# MEMS_RF.net
KiCad netlist of a schematic drawn in Altium Designer
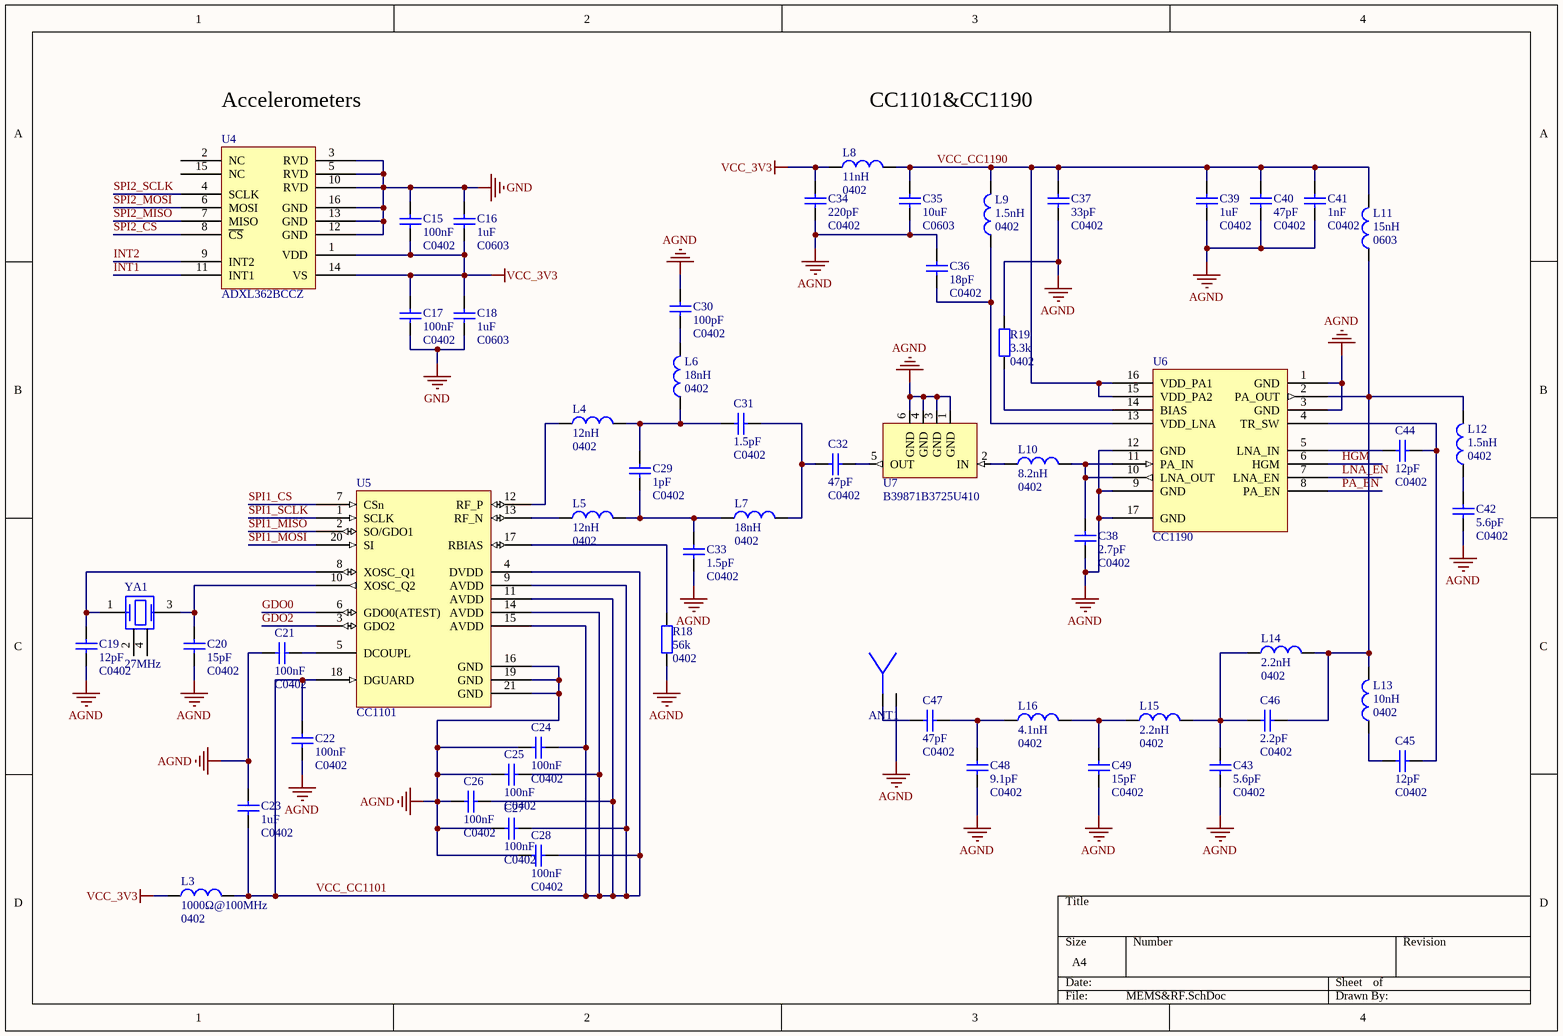
[diagram p0: MEMS&RF.SchDoc]

(export (version "E")
  (design (tool "Eeschema 10.0.6"))
  (components
    (comp (ref "ANT1")
      (value "ANT")
      (footprint "SMB-xg")
      (description "Antenna,GPS_ANT_IPX")
      (libsource (lib "RFID_CC1101_869MHz") (part "ANT"))
    )
    (comp (ref "C15")
      (value "100nF")
      (footprint "0402")
      (description "Capacitor (0402,X7R,100nF,DC 50V,±10%) TDK")
      (fields (field (name "PACKAGEREFERENCE") "C0402") (field (name "PUBLISHER") "Altium Limited"))
      (libsource (lib "GPS_NB") (part "C1005X7R1H104K050BE"))
    )
    (comp (ref "C16")
      (value "1uF")
      (footprint "1608[0603]")
      (description "Capacitor (0603,X5R,1uF,DC 10V,+/-10%) TDK")
      (fields (field (name "PACKAGEREFERENCE") "C0603") (field (name "PUBLISHER") "Altium Limited"))
      (libsource (lib "GPS_NB") (part "CGA3E2X5R1A105K080AA"))
    )
    (comp (ref "C17")
      (value "100nF")
      (footprint "0402")
      (description "Capacitor (0402,X7R,100nF,DC 50V,±10%) TDK")
      (fields (field (name "PACKAGEREFERENCE") "C0402") (field (name "PUBLISHER") "Altium Limited"))
      (libsource (lib "GPS_NB") (part "C1005X7R1H104K050BE"))
    )
    (comp (ref "C18")
      (value "1uF")
      (footprint "1608[0603]")
      (description "Capacitor (0603,X5R,1uF,DC 10V,+/-10%) TDK")
      (fields (field (name "PACKAGEREFERENCE") "C0603") (field (name "PUBLISHER") "Altium Limited"))
      (libsource (lib "GPS_NB") (part "CGA3E2X5R1A105K080AA"))
    )
    (comp (ref "C19")
      (value "12pF")
      (footprint "0402")
      (description "Capacitor (0402,NP0,12pF,DC 50V,±5%) Murata")
      (fields (field (name "PACKAGEREFERENCE") "C0402") (field (name "PUBLISHER") "Altium Limited"))
      (libsource (lib "RFID_CC1101_869MHz") (part "GRM1555C1H120JZ01D"))
    )
    (comp (ref "C20")
      (value "15pF")
      (footprint "0402")
      (description "Capacitor (0402,NP0,15pF,DC 50V,±5%) Murata")
      (fields (field (name "PACKAGEREFERENCE") "C0402") (field (name "PUBLISHER") "Altium Limited"))
      (libsource (lib "RFID_CC1101_869MHz") (part "GRM1555C1H150JZ01D"))
    )
    (comp (ref "C21")
      (value "100nF")
      (footprint "0402")
      (description "Capacitor (0402,X5R,100nF,DC 10V,±10%) Murata")
      (fields (field (name "PACKAGEREFERENCE") "C0402") (field (name "PUBLISHER") "Altium Limited"))
      (libsource (lib "RFID_CC1101_869MHz") (part "GRM155R71A104KA01D"))
    )
    (comp (ref "C22")
      (value "100nF")
      (footprint "0402")
      (description "Capacitor (0402,X5R,100nF,DC 10V,±10%) Murata")
      (fields (field (name "PACKAGEREFERENCE") "C0402") (field (name "PUBLISHER") "Altium Limited"))
      (libsource (lib "RFID_CC1101_869MHz") (part "GRM155R71A104KA01D"))
    )
    (comp (ref "C23")
      (value "1uF")
      (footprint "0402")
      (description "Capacitor (0402,X5R,1uF,DC 6.3V,±10%) Murata")
      (fields (field (name "PACKAGEREFERENCE") "C0402") (field (name "PUBLISHER") "Altium Limited"))
      (libsource (lib "RFID_CC1101_869MHz") (part "GRM155R60J105KE19D"))
    )
    (comp (ref "C24")
      (value "100nF")
      (footprint "0402")
      (description "Capacitor (0402,X5R,100nF,DC 10V,±10%) Murata")
      (fields (field (name "PACKAGEREFERENCE") "C0402") (field (name "PUBLISHER") "Altium Limited"))
      (libsource (lib "RFID_CC1101_869MHz") (part "GRM155R71A104KA01D"))
    )
    (comp (ref "C25")
      (value "100nF")
      (footprint "0402")
      (description "Capacitor (0402,X5R,100nF,DC 10V,±10%) Murata")
      (fields (field (name "PACKAGEREFERENCE") "C0402") (field (name "PUBLISHER") "Altium Limited"))
      (libsource (lib "RFID_CC1101_869MHz") (part "GRM155R71A104KA01D"))
    )
    (comp (ref "C26")
      (value "100nF")
      (footprint "0402")
      (description "Capacitor (0402,X5R,100nF,DC 10V,±10%) Murata")
      (fields (field (name "PACKAGEREFERENCE") "C0402") (field (name "PUBLISHER") "Altium Limited"))
      (libsource (lib "RFID_CC1101_869MHz") (part "GRM155R71A104KA01D"))
    )
    (comp (ref "C27")
      (value "100nF")
      (footprint "0402")
      (description "Capacitor (0402,X5R,100nF,DC 10V,±10%) Murata")
      (fields (field (name "PACKAGEREFERENCE") "C0402") (field (name "PUBLISHER") "Altium Limited"))
      (libsource (lib "RFID_CC1101_869MHz") (part "GRM155R71A104KA01D"))
    )
    (comp (ref "C28")
      (value "100nF")
      (footprint "0402")
      (description "Capacitor (0402,X5R,100nF,DC 10V,±10%) Murata")
      (fields (field (name "PACKAGEREFERENCE") "C0402") (field (name "PUBLISHER") "Altium Limited"))
      (libsource (lib "RFID_CC1101_869MHz") (part "GRM155R71A104KA01D"))
    )
    (comp (ref "C29")
      (value "1pF")
      (footprint "0402")
      (description "Capacitor (0402,NP0,1pF,DC 50V,±0.25pF) Murata")
      (fields (field (name "PACKAGEREFERENCE") "C0402") (field (name "PUBLISHER") "Altium Limited"))
      (libsource (lib "RFID_CC1101_869MHz") (part "GRM1555C1H1R0CZ01D"))
    )
    (comp (ref "C30")
      (value "100pF")
      (footprint "0402")
      (description "Capacitor (0402,NP0,100pF,DC 50V,±5%) Murata")
      (fields (field (name "PACKAGEREFERENCE") "C0402") (field (name "PUBLISHER") "Altium Limited"))
      (libsource (lib "RFID_CC1101_869MHz") (part "GRM1555C1H101JZ01D"))
    )
    (comp (ref "C31")
      (value "1.5pF")
      (footprint "0402")
      (description "Capacitor (0402,NP0,1.5pF,DC 50V,±0.25pF) Murata")
      (fields (field (name "PACKAGEREFERENCE") "C0402") (field (name "PUBLISHER") "Altium Limited"))
      (libsource (lib "RFID_CC1101_869MHz") (part "GRM1555C1H1R5CZ01D"))
    )
    (comp (ref "C32")
      (value "47pF")
      (footprint "0402")
      (description "Capacitor (0402,NP0,47pF,DC 50V,±5%) Murata")
      (fields (field (name "PACKAGEREFERENCE") "C0402") (field (name "PUBLISHER") "Altium Limited"))
      (libsource (lib "RFID_CC1101_869MHz") (part "GRM1555C1H470JZ01D"))
    )
    (comp (ref "C33")
      (value "1.5pF")
      (footprint "0402")
      (description "Capacitor (0402,NP0,1.5pF,DC 50V,±0.25pF) Murata")
      (fields (field (name "PACKAGEREFERENCE") "C0402") (field (name "PUBLISHER") "Altium Limited"))
      (libsource (lib "RFID_CC1101_869MHz") (part "GRM1555C1H1R5CZ01D"))
    )
    (comp (ref "C34")
      (value "220pF")
      (footprint "0402")
      (description "Capacitor (0402,NP0,220pF,DC 50V,±5%) Murata")
      (fields (field (name "PACKAGEREFERENCE") "C0402") (field (name "PUBLISHER") "Altium Limited"))
      (libsource (lib "RFID_CC1101_869MHz") (part "GRM1555C1H221JA01D"))
    )
    (comp (ref "C35")
      (value "10uF")
      (footprint "1608[0603]")
      (description "Capacitor (0603,X5R,10uF,DC 4V,+/-20%) Murata")
      (fields (field (name "PACKAGEREFERENCE") "C0603") (field (name "PUBLISHER") "Altium Limited"))
      (libsource (lib "RFID_CC1101_869MHz") (part "GRM188R60G106ME47D"))
    )
    (comp (ref "C36")
      (value "18pF")
      (footprint "0402")
      (description "Capacitor (0402,NP0,18pF,DC 25V,±5%) Murata")
      (fields (field (name "PACKAGEREFERENCE") "C0402") (field (name "PUBLISHER") "Altium Limited"))
      (libsource (lib "RFID_CC1101_869MHz") (part "GRM1555C1H180JZ01D"))
    )
    (comp (ref "C37")
      (value "33pF")
      (footprint "0402")
      (description "Capacitor (0402,NP0,33pF,DC 50V,±5%) Murata")
      (fields (field (name "PACKAGEREFERENCE") "C0402") (field (name "PUBLISHER") "Altium Limited"))
      (libsource (lib "RFID_CC1101_869MHz") (part "GRM1555C1H330JZ01D"))
    )
    (comp (ref "C38")
      (value "2.7pF")
      (footprint "0402")
      (description "Capacitor (0402,NP0,2.7pF,DC 50V,±0.25pF) Murata")
      (fields (field (name "PACKAGEREFERENCE") "C0402") (field (name "PUBLISHER") "Altium Limited"))
      (libsource (lib "RFID_CC1101_869MHz") (part "GRM1555C1H2R7CZ01D"))
    )
    (comp (ref "C39")
      (value "1uF")
      (footprint "0402")
      (description "Capacitor (0402,X5R,1uF,DC 6.3V,±10%) Murata")
      (fields (field (name "PACKAGEREFERENCE") "C0402") (field (name "PUBLISHER") "Altium Limited"))
      (libsource (lib "RFID_CC1101_869MHz") (part "GRM155R60J105KE19D"))
    )
    (comp (ref "C40")
      (value "47pF")
      (footprint "0402")
      (description "Capacitor (0402,NP0,47pF,DC 50V,±5%) Murata")
      (fields (field (name "PACKAGEREFERENCE") "C0402") (field (name "PUBLISHER") "Altium Limited"))
      (libsource (lib "RFID_CC1101_869MHz") (part "GRM1555C1H470JZ01D"))
    )
    (comp (ref "C41")
      (value "1nF")
      (footprint "0402")
      (description "Capacitor (0402,NP0,1nF,DC 50V,±5%) Murata")
      (fields (field (name "PACKAGEREFERENCE") "C0402") (field (name "PUBLISHER") "Altium Limited"))
      (libsource (lib "RFID_CC1101_869MHz") (part "GRM1555C1H102JA01D"))
    )
    (comp (ref "C42")
      (value "5.6pF")
      (footprint "0402")
      (description "Capacitor (0402,NP0,5.6pF,DC 50V,±0.25pF) Murata")
      (fields (field (name "PACKAGEREFERENCE") "C0402") (field (name "PUBLISHER") "Altium Limited"))
      (libsource (lib "RFID_CC1101_869MHz") (part "GRM1555C1H5R6CZ01D"))
    )
    (comp (ref "C43")
      (value "5.6pF")
      (footprint "0402")
      (description "Capacitor (0402,NP0,5.6pF,DC 50V,±0.25pF) Murata")
      (fields (field (name "PACKAGEREFERENCE") "C0402") (field (name "PUBLISHER") "Altium Limited"))
      (libsource (lib "RFID_CC1101_869MHz") (part "GRM1555C1H5R6CZ01D"))
    )
    (comp (ref "C44")
      (value "12pF")
      (footprint "0402")
      (description "Capacitor (0402,NP0,12pF,DC 50V,±5%) Murata")
      (fields (field (name "PACKAGEREFERENCE") "C0402") (field (name "PUBLISHER") "Altium Limited"))
      (libsource (lib "RFID_CC1101_869MHz") (part "GRM1555C1H120JZ01D"))
    )
    (comp (ref "C45")
      (value "12pF")
      (footprint "0402")
      (description "Capacitor (0402,NP0,12pF,DC 50V,±5%) Murata")
      (fields (field (name "PACKAGEREFERENCE") "C0402") (field (name "PUBLISHER") "Altium Limited"))
      (libsource (lib "RFID_CC1101_869MHz") (part "GRM1555C1H120JZ01D"))
    )
    (comp (ref "C46")
      (value "2.2pF")
      (footprint "0402")
      (description "Capacitor (0402,NP0,2.2pF,DC 50V,±0.25pF) Murata")
      (fields (field (name "PACKAGEREFERENCE") "C0402") (field (name "PUBLISHER") "Altium Limited"))
      (libsource (lib "RFID_CC1101_869MHz") (part "GRM1555C1H2R2CZ01"))
    )
    (comp (ref "C47")
      (value "47pF")
      (footprint "0402")
      (description "Capacitor (0402,NP0,47pF,DC 50V,±5%) Murata")
      (fields (field (name "PACKAGEREFERENCE") "C0402") (field (name "PUBLISHER") "Altium Limited"))
      (libsource (lib "RFID_CC1101_869MHz") (part "GRM1555C1H470JZ01D"))
    )
    (comp (ref "C48")
      (value "9.1pF")
      (footprint "0402")
      (description "Capacitor (0402,NP0,9.1pF,DC 50V,±0.25pF) Murata")
      (fields (field (name "PACKAGEREFERENCE") "C0402") (field (name "PUBLISHER") "Altium Limited"))
      (libsource (lib "RFID_CC1101_869MHz") (part "GRM1555C1H9R1CA01D"))
    )
    (comp (ref "C49")
      (value "15pF")
      (footprint "0402")
      (description "Capacitor (0402,NP0,15pF,DC 50V,±5%) Murata")
      (fields (field (name "PACKAGEREFERENCE") "C0402") (field (name "PUBLISHER") "Altium Limited"))
      (libsource (lib "RFID_CC1101_869MHz") (part "GRM1555C1H150JZ01D"))
    )
    (comp (ref "L3")
      (value "1000Ω@100MHz")
      (footprint "0402")
      (description "Inductor,EMI filter bead, 1000Ω@100MHz 250mA, 0402 1k ohms Tape GHz Band Gen Use, Murata")
      (fields (field (name "PACKAGEREFERENCE") "0402") (field (name "PUBLISHER") "Altium Limited"))
      (libsource (lib "RFID_CC1101_869MHz") (part "BLM15HG102SN1D"))
    )
    (comp (ref "L4")
      (value "12nH")
      (footprint "0402")
      (description "Inductor, 12n, 0402, ±5%, wire-wound type Murata")
      (fields (field (name "PACKAGEREFERENCE") "0402") (field (name "PUBLISHER") "Altium Limited"))
      (libsource (lib "RFID_CC1101_869MHz") (part "LQW15AN12NJ00D"))
    )
    (comp (ref "L5")
      (value "12nH")
      (footprint "0402")
      (description "Inductor, 12n, 0402, ±5%, wire-wound type Murata")
      (fields (field (name "PACKAGEREFERENCE") "0402") (field (name "PUBLISHER") "Altium Limited"))
      (libsource (lib "RFID_CC1101_869MHz") (part "LQW15AN12NJ00D"))
    )
    (comp (ref "L6")
      (value "18nH")
      (footprint "0402")
      (description "Inductor, 18n, 0402, ±5%, wire-wound type Murata")
      (fields (field (name "PACKAGEREFERENCE") "0402") (field (name "PUBLISHER") "Altium Limited"))
      (libsource (lib "RFID_CC1101_869MHz") (part "LQW15AN18NJ00D"))
    )
    (comp (ref "L7")
      (value "18nH")
      (footprint "0402")
      (description "Inductor, 18n, 0402, ±5%, wire-wound type Murata")
      (fields (field (name "PACKAGEREFERENCE") "0402") (field (name "PUBLISHER") "Altium Limited"))
      (libsource (lib "RFID_CC1101_869MHz") (part "LQW15AN18NJ00D"))
    )
    (comp (ref "L8")
      (value "11nH")
      (footprint "0402")
      (description "Inductor, 11n, 0402, ±5%, wire-wound type Murata")
      (fields (field (name "PACKAGEREFERENCE") "0402") (field (name "PUBLISHER") "Altium Limited"))
      (libsource (lib "RFID_CC1101_869MHz") (part "LQW15AN11NJ00"))
    )
    (comp (ref "L9")
      (value "1.5nH")
      (footprint "0402")
      (description "Inductor, 1n5, 0402, Monolithic type, +/-0.3 nH Murata")
      (fields (field (name "PACKAGEREFERENCE") "0402") (field (name "PUBLISHER") "Altium Limited"))
      (libsource (lib "RFID_CC1101_869MHz") (part "LQG15HS1N5S02D"))
    )
    (comp (ref "L10")
      (value "8.2nH")
      (footprint "0402")
      (description "Inductor, 8n2, 0402, ±5%\r\nMurata")
      (fields (field (name "PACKAGEREFERENCE") "0402") (field (name "PUBLISHER") "Altium Limited"))
      (libsource (lib "RFID_CC1101_869MHz") (part "LQG15HS8N2J02D"))
    )
    (comp (ref "L11")
      (value "15nH")
      (footprint "1608[0603]")
      (description "Inductor, 15n, 0603, ±5%, wire-wound type Murata")
      (fields (field (name "PACKAGEREFERENCE") "0603") (field (name "PUBLISHER") "Altium Limited"))
      (libsource (lib "RFID_CC1101_869MHz") (part "LQW18AN15NJ00"))
    )
    (comp (ref "L12")
      (value "1.5nH")
      (footprint "0402")
      (description "Inductor, 1n5, 0402, Monolithic type, +/-0.3 nH Murata")
      (fields (field (name "PACKAGEREFERENCE") "0402") (field (name "PUBLISHER") "Altium Limited"))
      (libsource (lib "RFID_CC1101_869MHz") (part "LQG15HS1N5S02D"))
    )
    (comp (ref "L13")
      (value "10nH")
      (footprint "0402")
      (description "Inductor, 10n, 0402, ±5%, wire-wound type Murata")
      (fields (field (name "PACKAGEREFERENCE") "0402") (field (name "PUBLISHER") "Altium Limited"))
      (libsource (lib "RFID_CC1101_869MHz") (part "LQW15AN10NJ00D"))
    )
    (comp (ref "L14")
      (value "2.2nH")
      (footprint "0402")
      (description "Inductor, 2n2, 0402, wire-wound type, +/- 0.2 nH Murata")
      (fields (field (name "PACKAGEREFERENCE") "0402") (field (name "PUBLISHER") "Altium Limited"))
      (libsource (lib "RFID_CC1101_869MHz") (part "LQW15AN2N2C10D"))
    )
    (comp (ref "L15")
      (value "2.2nH")
      (footprint "0402")
      (description "Inductor, 2n2, 0402, wire-wound type, +/- 0.2 nH Murata")
      (fields (field (name "PACKAGEREFERENCE") "0402") (field (name "PUBLISHER") "Altium Limited"))
      (libsource (lib "RFID_CC1101_869MHz") (part "LQW15AN2N2C10D"))
    )
    (comp (ref "L16")
      (value "4.1nH")
      (footprint "0402")
      (description "Inductor, 4n1, 0402, +/-0.2nH, wire-wound type Murata")
      (fields (field (name "PACKAGEREFERENCE") "0402") (field (name "PUBLISHER") "Altium Limited"))
      (libsource (lib "RFID_CC1101_869MHz") (part "LQW15AN4N1C00"))
    )
    (comp (ref "R18")
      (value "56k")
      (footprint "RESC1005X04N")
      (description "Resistor, 56k ohms, 0402, ±1% Koa")
      (fields (field (name "PACKAGEREFERENCE") "0402"))
      (libsource (lib "RFID_CC1101_869MHz") (part "RK73H1ETTP5602F"))
    )
    (comp (ref "R19")
      (value "3.3k")
      (footprint "RESC1005X04N")
      (description "Resistor, 3.3k ohms, 0402, ±1% Koa")
      (fields (field (name "PACKAGEREFERENCE") "0402"))
      (libsource (lib "RFID_CC1101_869MHz") (part "RK73H1ETTP3301F"))
    )
    (comp (ref "U4")
      (value "ADXL362BCCZ")
      (footprint "LGA_CC-16-4")
      (description "ADXL362, LGA, CC-16-4.")
      (libsource (lib "GPS_NB") (part "ADXL362BCCZ"))
    )
    (comp (ref "U5")
      (value "CC1101")
      (footprint "QFN50P400X400X100_HS-21N")
      (description "Low-Power Sub-1GHz RF Transceiver")
      (libsource (lib "RFID_CC1101_869MHz") (part "CC1101"))
    )
    (comp (ref "U6")
      (value "CC1190")
      (footprint "QFN65P400X400X100_HS-17N")
      (description "850– 950MHzRFFrontEnd")
      (libsource (lib "RFID_CC1101_869MHz") (part "CC1190"))
    )
    (comp (ref "U7")
      (value "B39871B3725U410")
      (footprint "DCC6C")
      (libsource (lib "RFID_CC1101_869MHz") (part "B39871B3725U410"))
    )
    (comp (ref "YA1")
      (value "27MHz")
      (footprint "XTAL-SMT-4P")
      (description "Crystal, 27.000000MHz, 10.0pF, 50 ohms max, NDK")
      (libsource (lib "RFID_CC1101_869MHz") (part "NX3225GA"))
    )
  )
  (nets
    (net (code "1") (name "/GDO0") (class "Default")
      (node (ref "U5") (pin "6") (pinfunction "GDO0(ATEST)_6") (pintype "bidirectional"))
    )
    (net (code "2") (name "/GDO2") (class "Default")
      (node (ref "U5") (pin "3") (pinfunction "GDO2_3") (pintype "bidirectional"))
    )
    (net (code "3") (name "/HGM") (class "Default")
      (node (ref "U6") (pin "6") (pinfunction "HGM_6") (pintype "passive"))
    )
    (net (code "4") (name "/INT1") (class "Default")
      (node (ref "U4") (pin "11") (pinfunction "INT1_11") (pintype "passive"))
    )
    (net (code "5") (name "/INT2") (class "Default")
      (node (ref "U4") (pin "9") (pinfunction "INT2_9") (pintype "passive"))
    )
    (net (code "6") (name "/LNA_EN") (class "Default")
      (node (ref "U6") (pin "7") (pinfunction "LNA_EN_7") (pintype "passive"))
    )
    (net (code "7") (name "/PA_EN") (class "Default")
      (node (ref "U6") (pin "8") (pinfunction "PA_EN_8") (pintype "passive"))
    )
    (net (code "8") (name "/SPI1_CS") (class "Default")
      (node (ref "U5") (pin "7") (pinfunction "CSn_7") (pintype "input"))
    )
    (net (code "9") (name "/SPI1_MISO") (class "Default")
      (node (ref "U5") (pin "2") (pinfunction "SO/GDO1_2") (pintype "bidirectional"))
    )
    (net (code "10") (name "/SPI1_MOSI") (class "Default")
      (node (ref "U5") (pin "20") (pinfunction "SI_20") (pintype "input"))
    )
    (net (code "11") (name "/SPI1_SCLK") (class "Default")
      (node (ref "U5") (pin "1") (pinfunction "SCLK_1") (pintype "input"))
    )
    (net (code "12") (name "/SPI2_CS") (class "Default")
      (node (ref "U4") (pin "8") (pinfunction "~{CS}_8") (pintype "passive"))
    )
    (net (code "13") (name "/SPI2_MISO") (class "Default")
      (node (ref "U4") (pin "7") (pinfunction "MISO_7") (pintype "passive"))
    )
    (net (code "14") (name "/SPI2_MOSI") (class "Default")
      (node (ref "U4") (pin "6") (pinfunction "MOSI_6") (pintype "passive"))
    )
    (net (code "15") (name "/SPI2_SCLK") (class "Default")
      (node (ref "U4") (pin "4") (pinfunction "SCLK_4") (pintype "passive"))
    )
    (net (code "16") (name "/VCC_CC1101") (class "Default")
      (node (ref "C22") (pin "2") (pinfunction "2_2") (pintype "passive"))
      (node (ref "C23") (pin "1") (pinfunction "1_1") (pintype "passive"))
      (node (ref "C24") (pin "1") (pinfunction "1_1") (pintype "passive"))
      (node (ref "C25") (pin "1") (pinfunction "1_1") (pintype "passive"))
      (node (ref "C26") (pin "1") (pinfunction "1_1") (pintype "passive"))
      (node (ref "C27") (pin "1") (pinfunction "1_1") (pintype "passive"))
      (node (ref "C28") (pin "1") (pinfunction "1_1") (pintype "passive"))
      (node (ref "L3") (pin "2") (pinfunction "2_2") (pintype "passive"))
      (node (ref "U5") (pin "11") (pinfunction "AVDD_11") (pintype "power_in"))
      (node (ref "U5") (pin "14") (pinfunction "AVDD_14") (pintype "power_in"))
      (node (ref "U5") (pin "15") (pinfunction "AVDD_15") (pintype "power_in"))
      (node (ref "U5") (pin "18") (pinfunction "DGUARD_18") (pintype "input"))
      (node (ref "U5") (pin "4") (pinfunction "DVDD_4") (pintype "power_in"))
      (node (ref "U5") (pin "9") (pinfunction "AVDD_9") (pintype "power_in"))
    )
    (net (code "17") (name "/VCC_CC1190") (class "Default")
      (node (ref "C35") (pin "2") (pinfunction "2_2") (pintype "passive"))
      (node (ref "C37") (pin "2") (pinfunction "2_2") (pintype "passive"))
      (node (ref "C39") (pin "2") (pinfunction "2_2") (pintype "passive"))
      (node (ref "C40") (pin "2") (pinfunction "2_2") (pintype "passive"))
      (node (ref "C41") (pin "2") (pinfunction "2_2") (pintype "passive"))
      (node (ref "L11") (pin "2") (pinfunction "2_2") (pintype "passive"))
      (node (ref "L8") (pin "2") (pinfunction "2_2") (pintype "passive"))
      (node (ref "L9") (pin "2") (pinfunction "2_2") (pintype "passive"))
      (node (ref "U6") (pin "15") (pinfunction "VDD_PA2_15") (pintype "power_in"))
      (node (ref "U6") (pin "16") (pinfunction "VDD_PA1_16") (pintype "power_in"))
    )
    (net (code "18") (name "AGND") (class "Default")
      (node (ref "ANT1") (pin "2") (pinfunction "GND_2") (pintype "power_in"))
      (node (ref "C19") (pin "1") (pinfunction "1_1") (pintype "passive"))
      (node (ref "C20") (pin "1") (pinfunction "1_1") (pintype "passive"))
      (node (ref "C21") (pin "1") (pinfunction "1_1") (pintype "passive"))
      (node (ref "C22") (pin "1") (pinfunction "1_1") (pintype "passive"))
      (node (ref "C23") (pin "2") (pinfunction "2_2") (pintype "passive"))
      (node (ref "C24") (pin "2") (pinfunction "2_2") (pintype "passive"))
      (node (ref "C25") (pin "2") (pinfunction "2_2") (pintype "passive"))
      (node (ref "C26") (pin "2") (pinfunction "2_2") (pintype "passive"))
      (node (ref "C27") (pin "2") (pinfunction "2_2") (pintype "passive"))
      (node (ref "C28") (pin "2") (pinfunction "2_2") (pintype "passive"))
      (node (ref "C30") (pin "2") (pinfunction "2_2") (pintype "passive"))
      (node (ref "C33") (pin "1") (pinfunction "1_1") (pintype "passive"))
      (node (ref "C34") (pin "1") (pinfunction "1_1") (pintype "passive"))
      (node (ref "C35") (pin "1") (pinfunction "1_1") (pintype "passive"))
      (node (ref "C36") (pin "2") (pinfunction "2_2") (pintype "passive"))
      (node (ref "C37") (pin "1") (pinfunction "1_1") (pintype "passive"))
      (node (ref "C38") (pin "1") (pinfunction "1_1") (pintype "passive"))
      (node (ref "C39") (pin "1") (pinfunction "1_1") (pintype "passive"))
      (node (ref "C40") (pin "1") (pinfunction "1_1") (pintype "passive"))
      (node (ref "C41") (pin "1") (pinfunction "1_1") (pintype "passive"))
      (node (ref "C42") (pin "1") (pinfunction "1_1") (pintype "passive"))
      (node (ref "C43") (pin "1") (pinfunction "1_1") (pintype "passive"))
      (node (ref "C48") (pin "1") (pinfunction "1_1") (pintype "passive"))
      (node (ref "C49") (pin "1") (pinfunction "1_1") (pintype "passive"))
      (node (ref "R18") (pin "1") (pinfunction "1_1") (pintype "passive"))
      (node (ref "R19") (pin "2") (pinfunction "2_2") (pintype "passive"))
      (node (ref "U5") (pin "16") (pinfunction "GND_16") (pintype "power_in"))
      (node (ref "U5") (pin "19") (pinfunction "GND_19") (pintype "power_in"))
      (node (ref "U5") (pin "21") (pinfunction "GND_21") (pintype "power_in"))
      (node (ref "U6") (pin "1") (pinfunction "GND_1") (pintype "power_in"))
      (node (ref "U6") (pin "12") (pinfunction "GND_12") (pintype "power_in"))
      (node (ref "U6") (pin "17") (pinfunction "GND_17") (pintype "power_in"))
      (node (ref "U6") (pin "3") (pinfunction "GND_3") (pintype "power_in"))
      (node (ref "U6") (pin "9") (pinfunction "GND_9") (pintype "power_in"))
      (node (ref "U7") (pin "1") (pinfunction "GND_1") (pintype "power_in"))
      (node (ref "U7") (pin "3") (pinfunction "GND_3") (pintype "power_in"))
      (node (ref "U7") (pin "4") (pinfunction "GND_4") (pintype "power_in"))
      (node (ref "U7") (pin "6") (pinfunction "GND_6") (pintype "power_in"))
    )
    (net (code "19") (name "GND") (class "Default")
      (node (ref "C15") (pin "1") (pinfunction "1_1") (pintype "passive"))
      (node (ref "C16") (pin "2") (pinfunction "2_2") (pintype "passive"))
      (node (ref "C17") (pin "2") (pinfunction "2_2") (pintype "passive"))
      (node (ref "C18") (pin "1") (pinfunction "1_1") (pintype "passive"))
      (node (ref "U4") (pin "10") (pinfunction "RVD_10") (pintype "passive"))
      (node (ref "U4") (pin "12") (pinfunction "GND_12") (pintype "passive"))
      (node (ref "U4") (pin "13") (pinfunction "GND_13") (pintype "passive"))
      (node (ref "U4") (pin "16") (pinfunction "GND_16") (pintype "passive"))
      (node (ref "U4") (pin "3") (pinfunction "RVD_3") (pintype "passive"))
      (node (ref "U4") (pin "5") (pinfunction "RVD_5") (pintype "passive"))
    )
    (net (code "20") (name "Net-(ANT1-Antenna)") (class "Default")
      (node (ref "ANT1") (pin "1") (pinfunction "Antenna_1") (pintype "passive"))
      (node (ref "C47") (pin "1") (pinfunction "1_1") (pintype "passive"))
    )
    (net (code "21") (name "Net-(C29-Pad1)") (class "Default")
      (node (ref "C29") (pin "1") (pinfunction "1_1") (pintype "passive"))
      (node (ref "C33") (pin "2") (pinfunction "2_2") (pintype "passive"))
      (node (ref "L5") (pin "2") (pinfunction "2_2") (pintype "passive"))
      (node (ref "L7") (pin "1") (pinfunction "1_1") (pintype "passive"))
    )
    (net (code "22") (name "Net-(C29-Pad2)") (class "Default")
      (node (ref "C29") (pin "2") (pinfunction "2_2") (pintype "passive"))
      (node (ref "C31") (pin "1") (pinfunction "1_1") (pintype "passive"))
      (node (ref "L4") (pin "2") (pinfunction "2_2") (pintype "passive"))
      (node (ref "L6") (pin "1") (pinfunction "1_1") (pintype "passive"))
    )
    (net (code "23") (name "Net-(C30-Pad1)") (class "Default")
      (node (ref "C30") (pin "1") (pinfunction "1_1") (pintype "passive"))
      (node (ref "L6") (pin "2") (pinfunction "2_2") (pintype "passive"))
    )
    (net (code "24") (name "Net-(C31-Pad2)") (class "Default")
      (node (ref "C31") (pin "2") (pinfunction "2_2") (pintype "passive"))
      (node (ref "C32") (pin "1") (pinfunction "1_1") (pintype "passive"))
      (node (ref "L7") (pin "2") (pinfunction "2_2") (pintype "passive"))
    )
    (net (code "25") (name "Net-(C42-Pad2)") (class "Default")
      (node (ref "C42") (pin "2") (pinfunction "2_2") (pintype "passive"))
      (node (ref "L12") (pin "1") (pinfunction "1_1") (pintype "passive"))
    )
    (net (code "26") (name "Net-(C43-Pad2)") (class "Default")
      (node (ref "C43") (pin "2") (pinfunction "2_2") (pintype "passive"))
      (node (ref "C46") (pin "1") (pinfunction "1_1") (pintype "passive"))
      (node (ref "L14") (pin "1") (pinfunction "1_1") (pintype "passive"))
      (node (ref "L15") (pin "2") (pinfunction "2_2") (pintype "passive"))
    )
    (net (code "27") (name "Net-(C45-Pad1)") (class "Default")
      (node (ref "C45") (pin "1") (pinfunction "1_1") (pintype "passive"))
      (node (ref "L13") (pin "1") (pinfunction "1_1") (pintype "passive"))
    )
    (net (code "28") (name "Net-(C47-Pad2)") (class "Default")
      (node (ref "C47") (pin "2") (pinfunction "2_2") (pintype "passive"))
      (node (ref "C48") (pin "2") (pinfunction "2_2") (pintype "passive"))
      (node (ref "L16") (pin "1") (pinfunction "1_1") (pintype "passive"))
    )
    (net (code "29") (name "Net-(C49-Pad2)") (class "Default")
      (node (ref "C49") (pin "2") (pinfunction "2_2") (pintype "passive"))
      (node (ref "L15") (pin "1") (pinfunction "1_1") (pintype "passive"))
      (node (ref "L16") (pin "2") (pinfunction "2_2") (pintype "passive"))
    )
    (net (code "30") (name "Net-(U5-DCOUPL)") (class "Default")
      (node (ref "C21") (pin "2") (pinfunction "2_2") (pintype "passive"))
      (node (ref "U5") (pin "5") (pinfunction "DCOUPL_5") (pintype "power_in"))
    )
    (net (code "31") (name "Net-(U5-RBIAS)") (class "Default")
      (node (ref "R18") (pin "2") (pinfunction "2_2") (pintype "passive"))
      (node (ref "U5") (pin "17") (pinfunction "RBIAS_17") (pintype "bidirectional"))
    )
    (net (code "32") (name "Net-(U5-RF_N)") (class "Default")
      (node (ref "L5") (pin "1") (pinfunction "1_1") (pintype "passive"))
      (node (ref "U5") (pin "13") (pinfunction "RF_N_13") (pintype "bidirectional"))
    )
    (net (code "33") (name "Net-(U5-RF_P)") (class "Default")
      (node (ref "L4") (pin "1") (pinfunction "1_1") (pintype "passive"))
      (node (ref "U5") (pin "12") (pinfunction "RF_P_12") (pintype "bidirectional"))
    )
    (net (code "34") (name "Net-(U5-XOSC_Q1)") (class "Default")
      (node (ref "C19") (pin "2") (pinfunction "2_2") (pintype "passive"))
      (node (ref "U5") (pin "8") (pinfunction "XOSC_Q1_8") (pintype "bidirectional"))
      (node (ref "YA1") (pin "1") (pinfunction "1_1") (pintype "passive"))
    )
    (net (code "35") (name "Net-(U5-XOSC_Q2)") (class "Default")
      (node (ref "C20") (pin "2") (pinfunction "2_2") (pintype "passive"))
      (node (ref "U5") (pin "10") (pinfunction "XOSC_Q2_10") (pintype "output"))
      (node (ref "YA1") (pin "3") (pinfunction "3_3") (pintype "passive"))
    )
    (net (code "36") (name "Net-(U6-BIAS)") (class "Default")
      (node (ref "R19") (pin "1") (pinfunction "1_1") (pintype "passive"))
      (node (ref "U6") (pin "14") (pinfunction "BIAS_14") (pintype "passive"))
    )
    (net (code "37") (name "Net-(U6-LNA_IN)") (class "Default")
      (node (ref "C44") (pin "1") (pinfunction "1_1") (pintype "passive"))
      (node (ref "U6") (pin "5") (pinfunction "LNA_IN_5") (pintype "passive"))
    )
    (net (code "38") (name "Net-(U6-LNA_OUT)") (class "Default")
      (node (ref "C38") (pin "2") (pinfunction "2_2") (pintype "passive"))
      (node (ref "L10") (pin "2") (pinfunction "2_2") (pintype "passive"))
      (node (ref "U6") (pin "10") (pinfunction "LNA_OUT_10") (pintype "output"))
      (node (ref "U6") (pin "11") (pinfunction "PA_IN_11") (pintype "input"))
    )
    (net (code "39") (name "Net-(U6-PA_OUT)") (class "Default")
      (node (ref "C46") (pin "2") (pinfunction "2_2") (pintype "passive"))
      (node (ref "L11") (pin "1") (pinfunction "1_1") (pintype "passive"))
      (node (ref "L12") (pin "2") (pinfunction "2_2") (pintype "passive"))
      (node (ref "L13") (pin "2") (pinfunction "2_2") (pintype "passive"))
      (node (ref "L14") (pin "2") (pinfunction "2_2") (pintype "passive"))
      (node (ref "U6") (pin "2") (pinfunction "PA_OUT_2") (pintype "output"))
    )
    (net (code "40") (name "Net-(U6-TR_SW)") (class "Default")
      (node (ref "C44") (pin "2") (pinfunction "2_2") (pintype "passive"))
      (node (ref "C45") (pin "2") (pinfunction "2_2") (pintype "passive"))
      (node (ref "U6") (pin "4") (pinfunction "TR_SW_4") (pintype "passive"))
    )
    (net (code "41") (name "Net-(U6-VDD_LNA)") (class "Default")
      (node (ref "C36") (pin "1") (pinfunction "1_1") (pintype "passive"))
      (node (ref "L9") (pin "1") (pinfunction "1_1") (pintype "passive"))
      (node (ref "U6") (pin "13") (pinfunction "VDD_LNA_13") (pintype "power_in"))
    )
    (net (code "42") (name "Net-(U7-IN)") (class "Default")
      (node (ref "L10") (pin "1") (pinfunction "1_1") (pintype "passive"))
      (node (ref "U7") (pin "2") (pinfunction "IN_2") (pintype "input"))
    )
    (net (code "43") (name "Net-(U7-OUT)") (class "Default")
      (node (ref "C32") (pin "2") (pinfunction "2_2") (pintype "passive"))
      (node (ref "U7") (pin "5") (pinfunction "OUT_5") (pintype "output"))
    )
    (net (code "44") (name "VCC_3V3") (class "Default")
      (node (ref "C15") (pin "2") (pinfunction "2_2") (pintype "passive"))
      (node (ref "C16") (pin "1") (pinfunction "1_1") (pintype "passive"))
      (node (ref "C17") (pin "1") (pinfunction "1_1") (pintype "passive"))
      (node (ref "C18") (pin "2") (pinfunction "2_2") (pintype "passive"))
      (node (ref "C34") (pin "2") (pinfunction "2_2") (pintype "passive"))
      (node (ref "L3") (pin "1") (pinfunction "1_1") (pintype "passive"))
      (node (ref "L8") (pin "1") (pinfunction "1_1") (pintype "passive"))
      (node (ref "U4") (pin "1") (pinfunction "VDD_1") (pintype "passive"))
      (node (ref "U4") (pin "14") (pinfunction "VS_14") (pintype "passive"))
    )
    (net (code "45") (name "unconnected-(U4-NC-Pad2)") (class "Default")
      (node (ref "U4") (pin "2") (pinfunction "NC_2") (pintype "passive"))
    )
    (net (code "46") (name "unconnected-(U4-NC-Pad15)") (class "Default")
      (node (ref "U4") (pin "15") (pinfunction "NC_15") (pintype "passive"))
    )
    (net (code "47") (name "unconnected-(YA1-Pad2)") (class "Default")
      (node (ref "YA1") (pin "2") (pinfunction "2_2") (pintype "passive"))
    )
    (net (code "48") (name "unconnected-(YA1-Pad4)") (class "Default")
      (node (ref "YA1") (pin "4") (pinfunction "4_4") (pintype "passive"))
    )
  )
)
